# design.net
KiCad netlist of a schematic drawn in Altium Designer
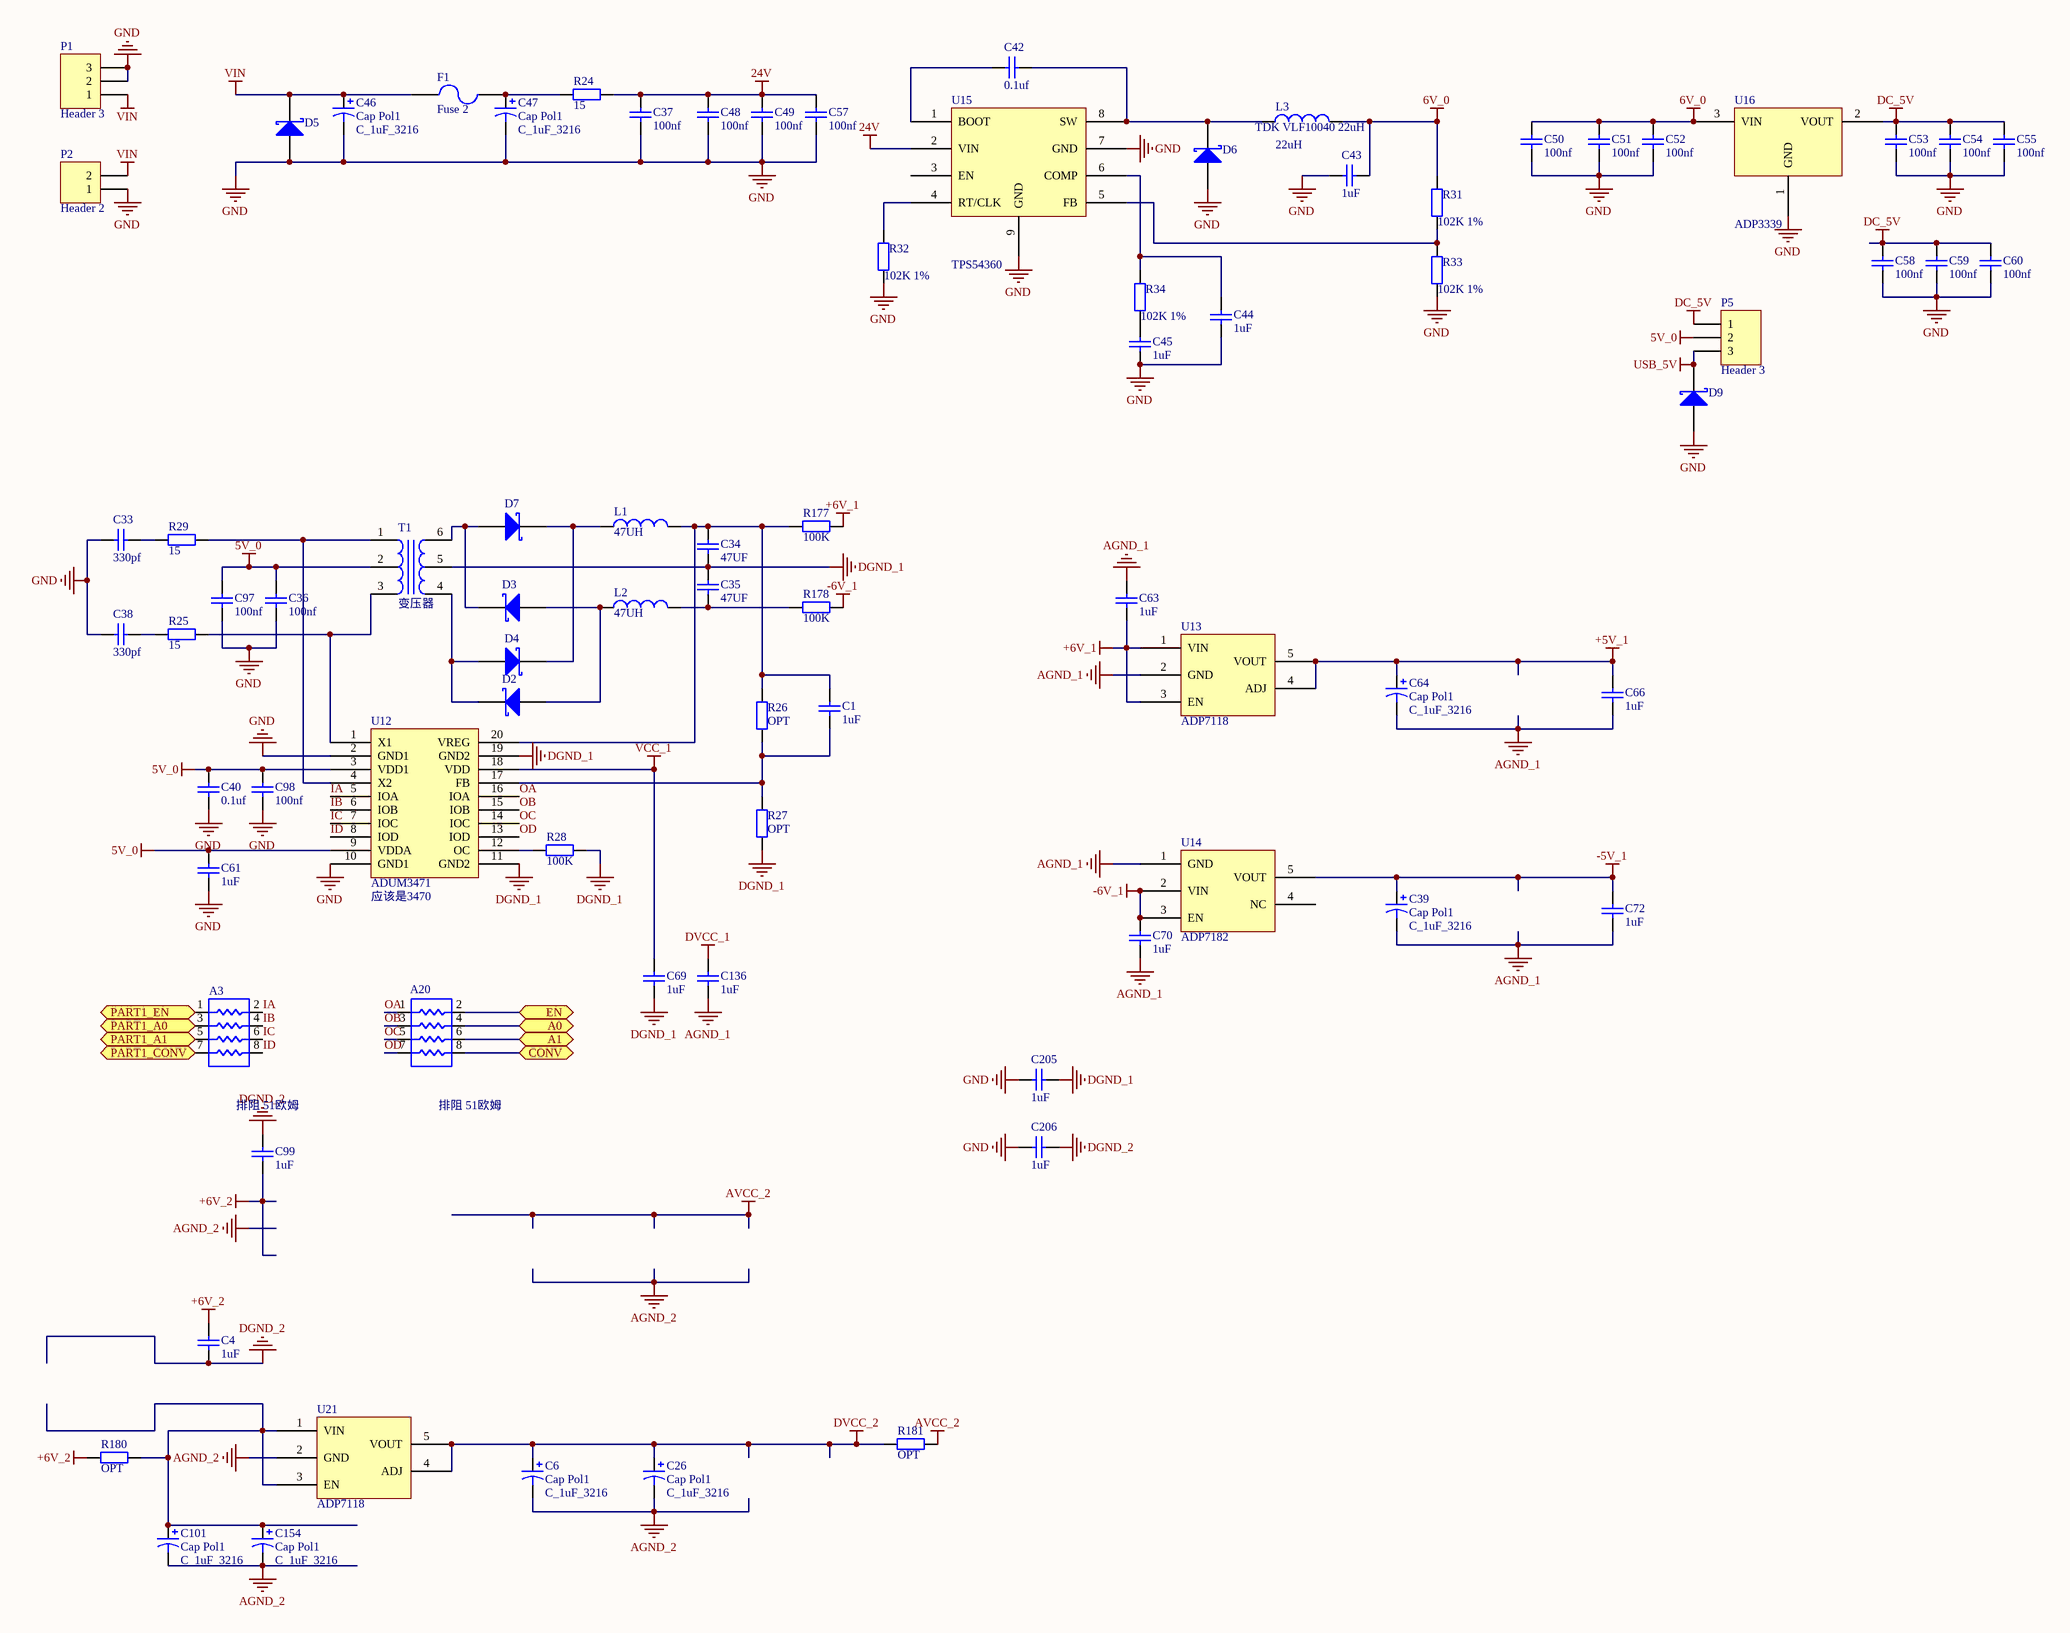
[diagram p0: 电源.SchDoc]

(export (version "E")
  (design (tool "Eeschema 10.0.6"))
  (components
    (comp (ref "A3")
      (value "排阻 51欧姆")
      (footprint "RCA03-4D")
      (libsource (lib "AD7606V23A") (part "RESPACK5"))
    )
    (comp (ref "A20")
      (value "排阻 51欧姆")
      (footprint "RCA03-4D")
      (libsource (lib "AD7606V23A") (part "RESPACK5"))
    )
    (comp (ref "C1")
      (value "1uF")
      (footprint "0805C")
      (description "Capacitor")
      (fields (field (name "PUBLISHER") "Altium Limited"))
      (libsource (lib "Miscellaneous Devices") (part "Cap"))
    )
    (comp (ref "C4")
      (value "1uF")
      (footprint "0805C")
      (description "Capacitor")
      (fields (field (name "PUBLISHER") "Altium Limited"))
      (libsource (lib "Miscellaneous Devices") (part "Cap"))
    )
    (comp (ref "C6")
      (value "Cap Pol1")
      (footprint "3216")
      (description "Polarized Capacitor (Radial)")
      (fields (field (name "ALTIUM_VALUE") "C_1uF_3216") (field (name "PUBLISHER") "Altium Limited"))
      (libsource (lib "AD7606V23A") (part "Cap Pol1"))
    )
    (comp (ref "C26")
      (value "Cap Pol1")
      (footprint "3216")
      (description "Polarized Capacitor (Radial)")
      (fields (field (name "ALTIUM_VALUE") "C_1uF_3216") (field (name "PUBLISHER") "Altium Limited"))
      (libsource (lib "AD7606V23A") (part "Cap Pol1"))
    )
    (comp (ref "C33")
      (value "330pf")
      (footprint "0805C")
      (description "Capacitor")
      (fields (field (name "Comment") "Cap") (field (name "PUBLISHER") "Altium Limited"))
      (libsource (lib "Miscellaneous Devices") (part "Cap"))
    )
    (comp (ref "C34")
      (value "47UF")
      (footprint "1812-C")
      (description "Capacitor")
      (fields (field (name "Comment") "Cap") (field (name "PUBLISHER") "Altium Limited"))
      (libsource (lib "Miscellaneous Devices") (part "Cap"))
    )
    (comp (ref "C35")
      (value "47UF")
      (footprint "1812-C")
      (description "Capacitor")
      (fields (field (name "Comment") "Cap") (field (name "PUBLISHER") "Altium Limited"))
      (libsource (lib "Miscellaneous Devices") (part "Cap"))
    )
    (comp (ref "C36")
      (value "100nf")
      (footprint "0805C")
      (description "Capacitor")
      (fields (field (name "Comment") "Cap") (field (name "PUBLISHER") "Altium Limited"))
      (libsource (lib "Miscellaneous Devices") (part "Cap"))
    )
    (comp (ref "C37")
      (value "100nf")
      (footprint "1812-C")
      (description "Capacitor")
      (fields (field (name "Comment") "Cap") (field (name "PUBLISHER") "Altium Limited"))
      (libsource (lib "Miscellaneous Devices") (part "Cap"))
    )
    (comp (ref "C38")
      (value "330pf")
      (footprint "0805C")
      (description "Capacitor")
      (fields (field (name "Comment") "Cap") (field (name "PUBLISHER") "Altium Limited"))
      (libsource (lib "Miscellaneous Devices") (part "Cap"))
    )
    (comp (ref "C39")
      (value "Cap Pol1")
      (footprint "3216")
      (description "Polarized Capacitor (Radial)")
      (fields (field (name "ALTIUM_VALUE") "C_1uF_3216") (field (name "PUBLISHER") "Altium Limited"))
      (libsource (lib "AD7606V23A") (part "Cap Pol1"))
    )
    (comp (ref "C40")
      (value "0.1uf")
      (footprint "0805C")
      (description "Capacitor")
      (fields (field (name "Comment") "Cap") (field (name "PUBLISHER") "Altium Limited"))
      (libsource (lib "Miscellaneous Devices") (part "Cap"))
    )
    (comp (ref "C42")
      (value "0.1uf")
      (footprint "独石电容")
      (description "Capacitor")
      (fields (field (name "Comment") "Cap") (field (name "PUBLISHER") "Altium Limited"))
      (libsource (lib "Miscellaneous Devices") (part "Cap"))
    )
    (comp (ref "C43")
      (value "1uF")
      (footprint "SMD-EC-F8")
      (description "Capacitor")
      (fields (field (name "PUBLISHER") "Altium Limited"))
      (libsource (lib "Miscellaneous Devices") (part "Cap"))
    )
    (comp (ref "C44")
      (value "1uF")
      (footprint "0805C")
      (description "Capacitor")
      (fields (field (name "PUBLISHER") "Altium Limited"))
      (libsource (lib "Miscellaneous Devices") (part "Cap"))
    )
    (comp (ref "C45")
      (value "1uF")
      (footprint "0805C")
      (description "Capacitor")
      (fields (field (name "PUBLISHER") "Altium Limited"))
      (libsource (lib "Miscellaneous Devices") (part "Cap"))
    )
    (comp (ref "C46")
      (value "Cap Pol1")
      (footprint "SMD-EC-F12.5")
      (description "Polarized Capacitor (Radial)")
      (fields (field (name "ALTIUM_VALUE") "C_1uF_3216") (field (name "PUBLISHER") "Altium Limited"))
      (libsource (lib "AD7606V23A") (part "Cap Pol1"))
    )
    (comp (ref "C47")
      (value "Cap Pol1")
      (footprint "0805C")
      (description "Polarized Capacitor (Radial)")
      (fields (field (name "ALTIUM_VALUE") "C_1uF_3216") (field (name "PUBLISHER") "Altium Limited"))
      (libsource (lib "AD7606V23A") (part "Cap Pol1"))
    )
    (comp (ref "C48")
      (value "100nf")
      (footprint "0805C")
      (description "Capacitor")
      (fields (field (name "Comment") "Cap") (field (name "PUBLISHER") "Altium Limited"))
      (libsource (lib "Miscellaneous Devices") (part "Cap"))
    )
    (comp (ref "C49")
      (value "100nf")
      (footprint "0805C")
      (description "Capacitor")
      (fields (field (name "Comment") "Cap") (field (name "PUBLISHER") "Altium Limited"))
      (libsource (lib "Miscellaneous Devices") (part "Cap"))
    )
    (comp (ref "C50")
      (value "100nf")
      (footprint "1812-C")
      (description "Capacitor")
      (fields (field (name "Comment") "Cap") (field (name "PUBLISHER") "Altium Limited"))
      (libsource (lib "Miscellaneous Devices") (part "Cap"))
    )
    (comp (ref "C51")
      (value "100nf")
      (footprint "0805C")
      (description "Capacitor")
      (fields (field (name "Comment") "Cap") (field (name "PUBLISHER") "Altium Limited"))
      (libsource (lib "Miscellaneous Devices") (part "Cap"))
    )
    (comp (ref "C52")
      (value "100nf")
      (footprint "0805C")
      (description "Capacitor")
      (fields (field (name "Comment") "Cap") (field (name "PUBLISHER") "Altium Limited"))
      (libsource (lib "Miscellaneous Devices") (part "Cap"))
    )
    (comp (ref "C53")
      (value "100nf")
      (footprint "1812-C")
      (description "Capacitor")
      (fields (field (name "Comment") "Cap") (field (name "PUBLISHER") "Altium Limited"))
      (libsource (lib "Miscellaneous Devices") (part "Cap"))
    )
    (comp (ref "C54")
      (value "100nf")
      (footprint "0805C")
      (description "Capacitor")
      (fields (field (name "Comment") "Cap") (field (name "PUBLISHER") "Altium Limited"))
      (libsource (lib "Miscellaneous Devices") (part "Cap"))
    )
    (comp (ref "C55")
      (value "100nf")
      (footprint "0805C")
      (description "Capacitor")
      (fields (field (name "Comment") "Cap") (field (name "PUBLISHER") "Altium Limited"))
      (libsource (lib "Miscellaneous Devices") (part "Cap"))
    )
    (comp (ref "C57")
      (value "100nf")
      (footprint "1812-C")
      (description "Capacitor")
      (fields (field (name "Comment") "Cap") (field (name "PUBLISHER") "Altium Limited"))
      (libsource (lib "Miscellaneous Devices") (part "Cap"))
    )
    (comp (ref "C58")
      (value "100nf")
      (footprint "0805C")
      (description "Capacitor")
      (fields (field (name "Comment") "Cap") (field (name "PUBLISHER") "Altium Limited"))
      (libsource (lib "Miscellaneous Devices") (part "Cap"))
    )
    (comp (ref "C59")
      (value "100nf")
      (footprint "0805C")
      (description "Capacitor")
      (fields (field (name "Comment") "Cap") (field (name "PUBLISHER") "Altium Limited"))
      (libsource (lib "Miscellaneous Devices") (part "Cap"))
    )
    (comp (ref "C60")
      (value "100nf")
      (footprint "0805C")
      (description "Capacitor")
      (fields (field (name "Comment") "Cap") (field (name "PUBLISHER") "Altium Limited"))
      (libsource (lib "Miscellaneous Devices") (part "Cap"))
    )
    (comp (ref "C61")
      (value "1uF")
      (footprint "0805C")
      (description "Capacitor")
      (fields (field (name "PUBLISHER") "Altium Limited"))
      (libsource (lib "Miscellaneous Devices") (part "Cap"))
    )
    (comp (ref "C63")
      (value "1uF")
      (footprint "0805C")
      (description "Capacitor")
      (fields (field (name "PUBLISHER") "Altium Limited"))
      (libsource (lib "Miscellaneous Devices") (part "Cap"))
    )
    (comp (ref "C64")
      (value "Cap Pol1")
      (footprint "3216")
      (description "Polarized Capacitor (Radial)")
      (fields (field (name "ALTIUM_VALUE") "C_1uF_3216") (field (name "PUBLISHER") "Altium Limited"))
      (libsource (lib "AD7606V23A") (part "Cap Pol1"))
    )
    (comp (ref "C66")
      (value "1uF")
      (footprint "0805C")
      (description "Capacitor")
      (fields (field (name "PUBLISHER") "Altium Limited"))
      (libsource (lib "Miscellaneous Devices") (part "Cap"))
    )
    (comp (ref "C69")
      (value "1uF")
      (footprint "0805C")
      (description "Capacitor")
      (fields (field (name "PUBLISHER") "Altium Limited"))
      (libsource (lib "Miscellaneous Devices") (part "Cap"))
    )
    (comp (ref "C70")
      (value "1uF")
      (footprint "0805C")
      (description "Capacitor")
      (fields (field (name "PUBLISHER") "Altium Limited"))
      (libsource (lib "Miscellaneous Devices") (part "Cap"))
    )
    (comp (ref "C72")
      (value "1uF")
      (footprint "0805C")
      (description "Capacitor")
      (fields (field (name "PUBLISHER") "Altium Limited"))
      (libsource (lib "Miscellaneous Devices") (part "Cap"))
    )
    (comp (ref "C97")
      (value "100nf")
      (footprint "0805C")
      (description "Capacitor")
      (fields (field (name "Comment") "Cap") (field (name "PUBLISHER") "Altium Limited"))
      (libsource (lib "Miscellaneous Devices") (part "Cap"))
    )
    (comp (ref "C98")
      (value "100nf")
      (footprint "0805C")
      (description "Capacitor")
      (fields (field (name "Comment") "Cap") (field (name "PUBLISHER") "Altium Limited"))
      (libsource (lib "Miscellaneous Devices") (part "Cap"))
    )
    (comp (ref "C99")
      (value "1uF")
      (footprint "0805C")
      (description "Capacitor")
      (fields (field (name "PUBLISHER") "Altium Limited"))
      (libsource (lib "Miscellaneous Devices") (part "Cap"))
    )
    (comp (ref "C101")
      (value "Cap Pol1")
      (footprint "3216")
      (description "Polarized Capacitor (Radial)")
      (fields (field (name "ALTIUM_VALUE") "C_1uF_3216") (field (name "PUBLISHER") "Altium Limited"))
      (libsource (lib "AD7606V23A") (part "Cap Pol1"))
    )
    (comp (ref "C136")
      (value "1uF")
      (footprint "0805C")
      (description "Capacitor")
      (fields (field (name "PUBLISHER") "Altium Limited"))
      (libsource (lib "Miscellaneous Devices") (part "Cap"))
    )
    (comp (ref "C154")
      (value "Cap Pol1")
      (footprint "3216")
      (description "Polarized Capacitor (Radial)")
      (fields (field (name "ALTIUM_VALUE") "C_1uF_3216") (field (name "PUBLISHER") "Altium Limited"))
      (libsource (lib "AD7606V23A") (part "Cap Pol1"))
    )
    (comp (ref "C205")
      (value "1uF")
      (footprint "7.5mm-C")
      (description "Capacitor")
      (fields (field (name "PUBLISHER") "Altium Limited"))
      (libsource (lib "Miscellaneous Devices") (part "Cap"))
    )
    (comp (ref "C206")
      (value "1uF")
      (footprint "7.5mm-C")
      (description "Capacitor")
      (fields (field (name "PUBLISHER") "Altium Limited"))
      (libsource (lib "Miscellaneous Devices") (part "Cap"))
    )
    (comp (ref "D2")
      (value "~")
      (footprint "FB1206")
      (description "Schottky Rectifier")
      (fields (field (name "PUBLISHER") "Altium Limited"))
      (libsource (lib "Miscellaneous Devices") (part "Diode 11DQ03"))
    )
    (comp (ref "D3")
      (value "~")
      (footprint "FB1206")
      (description "Schottky Rectifier")
      (fields (field (name "PUBLISHER") "Altium Limited"))
      (libsource (lib "Miscellaneous Devices") (part "Diode 11DQ03"))
    )
    (comp (ref "D4")
      (value "~")
      (footprint "FB1206")
      (description "Schottky Rectifier")
      (fields (field (name "PUBLISHER") "Altium Limited"))
      (libsource (lib "Miscellaneous Devices") (part "Diode 11DQ03"))
    )
    (comp (ref "D5")
      (value "~")
      (footprint "SMB1")
      (description "Schottky Rectifier")
      (fields (field (name "PUBLISHER") "Altium Limited"))
      (libsource (lib "Miscellaneous Devices") (part "Diode 11DQ03"))
    )
    (comp (ref "D6")
      (value "~")
      (footprint "SMA")
      (description "Schottky Rectifier")
      (fields (field (name "PUBLISHER") "Altium Limited"))
      (libsource (lib "Miscellaneous Devices") (part "Diode 11DQ03"))
    )
    (comp (ref "D7")
      (value "~")
      (footprint "FB1206")
      (description "Schottky Rectifier")
      (fields (field (name "PUBLISHER") "Altium Limited"))
      (libsource (lib "Miscellaneous Devices") (part "Diode 11DQ03"))
    )
    (comp (ref "D9")
      (value "~")
      (footprint "SMA")
      (description "Schottky Rectifier")
      (fields (field (name "PUBLISHER") "Altium Limited"))
      (libsource (lib "Miscellaneous Devices") (part "Diode 11DQ03"))
    )
    (comp (ref "F1")
      (value "Fuse 2")
      (footprint "1812-PPTC")
      (description "Fuse")
      (fields (field (name "PUBLISHER") "Altium Limited"))
      (libsource (lib "Miscellaneous Devices") (part "Fuse 2"))
    )
    (comp (ref "L1")
      (value "47UH")
      (footprint "1812-R")
      (description "Inductor")
      (fields (field (name "PUBLISHER") "Altium Limited"))
      (libsource (lib "Miscellaneous Devices") (part "Inductor"))
    )
    (comp (ref "L2")
      (value "47UH")
      (footprint "1812-R")
      (description "Inductor")
      (fields (field (name "PUBLISHER") "Altium Limited"))
      (libsource (lib "Miscellaneous Devices") (part "Inductor"))
    )
    (comp (ref "L3")
      (value "TDK VLF10040 22uH")
      (footprint "RH74")
      (description "Inductor")
      (fields (field (name "ALTIUM_VALUE") "22uH") (field (name "PUBLISHER") "Altium Limited"))
      (libsource (lib "Miscellaneous Devices") (part "Inductor"))
    )
    (comp (ref "P1")
      (value "Header 3")
      (footprint "DC-005A")
      (description "Header, 3-Pin")
      (fields (field (name "PUBLISHER") "Altium Limited"))
      (libsource (lib "Miscellaneous Connectors") (part "Header 3"))
    )
    (comp (ref "P2")
      (value "Header 2")
      (footprint "2EDGK-2P")
      (description "Header, 2-Pin")
      (fields (field (name "PUBLISHER") "Altium Limited"))
      (libsource (lib "Miscellaneous Connectors") (part "Header 2"))
    )
    (comp (ref "P5")
      (value "Header 3")
      (footprint "SIP03")
      (description "Header, 3-Pin")
      (fields (field (name "PUBLISHER") "Altium Limited"))
      (libsource (lib "") (part "Header 3_1"))
    )
    (comp (ref "R24")
      (value "15")
      (footprint "FB1206")
      (description "Resistor")
      (fields (field (name "Comment") "Res2") (field (name "PUBLISHER") "Altium Limited"))
      (libsource (lib "") (part "Res2_2"))
    )
    (comp (ref "R25")
      (value "15")
      (footprint "0805R")
      (description "Resistor")
      (fields (field (name "Comment") "Res2") (field (name "PUBLISHER") "Altium Limited"))
      (libsource (lib "") (part "Res2_2"))
    )
    (comp (ref "R26")
      (value "OPT")
      (footprint "0805R")
      (description "Resistor")
      (fields (field (name "Comment") "Res2") (field (name "PUBLISHER") "Altium Limited"))
      (libsource (lib "") (part "Res2_1"))
    )
    (comp (ref "R27")
      (value "OPT")
      (footprint "0805R")
      (description "Resistor")
      (fields (field (name "Comment") "Res2") (field (name "PUBLISHER") "Altium Limited"))
      (libsource (lib "") (part "Res2_1"))
    )
    (comp (ref "R28")
      (value "100K")
      (footprint "0805R")
      (description "Resistor")
      (fields (field (name "Comment") "Res2") (field (name "PUBLISHER") "Altium Limited"))
      (libsource (lib "") (part "Res2_2"))
    )
    (comp (ref "R29")
      (value "15")
      (footprint "0805R")
      (description "Resistor")
      (fields (field (name "Comment") "Res2") (field (name "PUBLISHER") "Altium Limited"))
      (libsource (lib "") (part "Res2_2"))
    )
    (comp (ref "R31")
      (value "102K 1%")
      (footprint "0805R")
      (description "Resistor")
      (fields (field (name "PUBLISHER") "Altium Limited"))
      (libsource (lib "Miscellaneous Devices") (part "Res2"))
    )
    (comp (ref "R32")
      (value "102K 1%")
      (footprint "0805R")
      (description "Resistor")
      (fields (field (name "PUBLISHER") "Altium Limited"))
      (libsource (lib "Miscellaneous Devices") (part "Res2"))
    )
    (comp (ref "R33")
      (value "102K 1%")
      (footprint "0805R")
      (description "Resistor")
      (fields (field (name "PUBLISHER") "Altium Limited"))
      (libsource (lib "Miscellaneous Devices") (part "Res2"))
    )
    (comp (ref "R34")
      (value "102K 1%")
      (footprint "0805R")
      (description "Resistor")
      (fields (field (name "PUBLISHER") "Altium Limited"))
      (libsource (lib "Miscellaneous Devices") (part "Res2"))
    )
    (comp (ref "R177")
      (value "100K")
      (footprint "0805R")
      (description "Resistor")
      (fields (field (name "Comment") "Res2") (field (name "PUBLISHER") "Altium Limited"))
      (libsource (lib "") (part "Res2_2"))
    )
    (comp (ref "R178")
      (value "100K")
      (footprint "0805R")
      (description "Resistor")
      (fields (field (name "Comment") "Res2") (field (name "PUBLISHER") "Altium Limited"))
      (libsource (lib "") (part "Res2_2"))
    )
    (comp (ref "R180")
      (value "OPT")
      (footprint "0805R")
      (description "Resistor")
      (fields (field (name "Comment") "Res2") (field (name "PUBLISHER") "Altium Limited"))
      (libsource (lib "") (part "Res2_2"))
    )
    (comp (ref "R181")
      (value "OPT")
      (footprint "0805R")
      (description "Resistor")
      (fields (field (name "Comment") "Res2") (field (name "PUBLISHER") "Altium Limited"))
      (libsource (lib "") (part "Res2_2"))
    )
    (comp (ref "T1") (value "变压器") (footprint "变压器") (libsource (lib "ic_lib") (part "变压器")))
    (comp (ref "U12") (value "ADUM3471") (footprint "SSOP20") (libsource (lib "ic_lib") (part "ADUM3471")))
    (comp (ref "U13") (value "ADP7118") (footprint "SOT-23-5") (libsource (lib "ic_lib") (part "ADP7118")))
    (comp (ref "U14") (value "ADP7182") (footprint "SOT-23-5") (libsource (lib "ic_lib") (part "ADP7182")))
    (comp (ref "U15") (value "TPS54360") (footprint "TPS54360") (libsource (lib "ic_lib") (part "TPS54360")))
    (comp (ref "U16") (value "ADP3339") (footprint "_SOT-223") (libsource (lib "ic_lib") (part "ADP3339")))
    (comp (ref "U21") (value "ADP7118") (footprint "SOT-23-5") (libsource (lib "ic_lib") (part "ADP7118")))
  )
  (nets
    (net (code "1") (name "+5V_1") (class "Default")
      (node (ref "C64") (pin "1") (pinfunction "1_1") (pintype "passive"))
      (node (ref "C66") (pin "1") (pinfunction "1_1") (pintype "passive"))
      (node (ref "U13") (pin "4") (pinfunction "ADJ_4") (pintype "passive"))
      (node (ref "U13") (pin "5") (pinfunction "VOUT_5") (pintype "passive"))
    )
    (net (code "2") (name "+6V_1") (class "Default")
      (node (ref "C63") (pin "2") (pinfunction "2_2") (pintype "passive"))
      (node (ref "R177") (pin "2") (pinfunction "2_2") (pintype "passive"))
      (node (ref "U13") (pin "1") (pinfunction "VIN_1") (pintype "passive"))
      (node (ref "U13") (pin "3") (pinfunction "EN_3") (pintype "passive"))
    )
    (net (code "3") (name "+6V_2") (class "Default")
      (node (ref "C4") (pin "1") (pinfunction "1_1") (pintype "passive"))
      (node (ref "C99") (pin "2") (pinfunction "2_2") (pintype "passive"))
      (node (ref "R180") (pin "1") (pinfunction "1_1") (pintype "passive"))
    )
    (net (code "4") (name "-5V_1") (class "Default")
      (node (ref "C39") (pin "1") (pinfunction "1_1") (pintype "passive"))
      (node (ref "C72") (pin "1") (pinfunction "1_1") (pintype "passive"))
      (node (ref "U14") (pin "5") (pinfunction "VOUT_5") (pintype "passive"))
    )
    (net (code "5") (name "-6V_1") (class "Default")
      (node (ref "C70") (pin "1") (pinfunction "1_1") (pintype "passive"))
      (node (ref "R178") (pin "2") (pinfunction "2_2") (pintype "passive"))
      (node (ref "U14") (pin "2") (pinfunction "VIN_2") (pintype "passive"))
      (node (ref "U14") (pin "3") (pinfunction "EN_3") (pintype "passive"))
    )
    (net (code "6") (name "/A0") (class "Default")
      (node (ref "A20") (pin "4") (pinfunction "4_4") (pintype "passive"))
    )
    (net (code "7") (name "/A1") (class "Default")
      (node (ref "A20") (pin "6") (pinfunction "8_6") (pintype "passive"))
    )
    (net (code "8") (name "/CONV") (class "Default")
      (node (ref "A20") (pin "8") (pinfunction "8_8") (pintype "passive"))
    )
    (net (code "9") (name "/EN") (class "Default")
      (node (ref "A20") (pin "2") (pinfunction "2_2") (pintype "passive"))
    )
    (net (code "10") (name "/IA") (class "Default")
      (node (ref "A3") (pin "2") (pinfunction "2_2") (pintype "passive"))
      (node (ref "U12") (pin "5") (pinfunction "IOA_5") (pintype "passive"))
    )
    (net (code "11") (name "/IB") (class "Default")
      (node (ref "A3") (pin "4") (pinfunction "4_4") (pintype "passive"))
      (node (ref "U12") (pin "6") (pinfunction "IOB_6") (pintype "passive"))
    )
    (net (code "12") (name "/IC") (class "Default")
      (node (ref "A3") (pin "6") (pinfunction "8_6") (pintype "passive"))
      (node (ref "U12") (pin "7") (pinfunction "IOC_7") (pintype "passive"))
    )
    (net (code "13") (name "/ID") (class "Default")
      (node (ref "A3") (pin "8") (pinfunction "8_8") (pintype "passive"))
      (node (ref "U12") (pin "8") (pinfunction "IOD_8") (pintype "passive"))
    )
    (net (code "14") (name "/OA") (class "Default")
      (node (ref "A20") (pin "1") (pinfunction "1_1") (pintype "passive"))
      (node (ref "U12") (pin "16") (pinfunction "IOA_16") (pintype "passive"))
    )
    (net (code "15") (name "/OB") (class "Default")
      (node (ref "A20") (pin "3") (pinfunction "3_3") (pintype "passive"))
      (node (ref "U12") (pin "15") (pinfunction "IOB_15") (pintype "passive"))
    )
    (net (code "16") (name "/OC") (class "Default")
      (node (ref "A20") (pin "5") (pinfunction "5_5") (pintype "passive"))
      (node (ref "U12") (pin "14") (pinfunction "IOC_14") (pintype "passive"))
    )
    (net (code "17") (name "/OD") (class "Default")
      (node (ref "A20") (pin "7") (pinfunction "7_7") (pintype "passive"))
      (node (ref "U12") (pin "13") (pinfunction "IOD_13") (pintype "passive"))
    )
    (net (code "18") (name "/PART1_A0") (class "Default")
      (node (ref "A3") (pin "3") (pinfunction "3_3") (pintype "passive"))
    )
    (net (code "19") (name "/PART1_A1") (class "Default")
      (node (ref "A3") (pin "5") (pinfunction "5_5") (pintype "passive"))
    )
    (net (code "20") (name "/PART1_CONV") (class "Default")
      (node (ref "A3") (pin "7") (pinfunction "7_7") (pintype "passive"))
    )
    (net (code "21") (name "/PART1_EN") (class "Default")
      (node (ref "A3") (pin "1") (pinfunction "1_1") (pintype "passive"))
    )
    (net (code "22") (name "5V_0") (class "Default")
      (node (ref "C36") (pin "2") (pinfunction "2_2") (pintype "passive"))
      (node (ref "C40") (pin "1") (pinfunction "1_1") (pintype "passive"))
      (node (ref "C61") (pin "1") (pinfunction "1_1") (pintype "passive"))
      (node (ref "C97") (pin "2") (pinfunction "2_2") (pintype "passive"))
      (node (ref "C98") (pin "2") (pinfunction "2_2") (pintype "passive"))
      (node (ref "P5") (pin "2") (pinfunction "2_2") (pintype "passive"))
      (node (ref "T1") (pin "2") (pinfunction "2_2") (pintype "passive"))
      (node (ref "U12") (pin "3") (pinfunction "VDD1_3") (pintype "passive"))
      (node (ref "U12") (pin "9") (pinfunction "VDDA_9") (pintype "passive"))
    )
    (net (code "23") (name "6V_0") (class "Default")
      (node (ref "C43") (pin "1") (pinfunction "1_1") (pintype "passive"))
      (node (ref "C50") (pin "2") (pinfunction "2_2") (pintype "passive"))
      (node (ref "C51") (pin "2") (pinfunction "2_2") (pintype "passive"))
      (node (ref "C52") (pin "2") (pinfunction "2_2") (pintype "passive"))
      (node (ref "L3") (pin "2") (pinfunction "2_2") (pintype "passive"))
      (node (ref "R31") (pin "2") (pinfunction "2_2") (pintype "passive"))
      (node (ref "U16") (pin "3") (pinfunction "VIN_3") (pintype "passive"))
    )
    (net (code "24") (name "24V") (class "Default")
      (node (ref "C37") (pin "2") (pinfunction "2_2") (pintype "passive"))
      (node (ref "C48") (pin "2") (pinfunction "2_2") (pintype "passive"))
      (node (ref "C49") (pin "2") (pinfunction "2_2") (pintype "passive"))
      (node (ref "C57") (pin "2") (pinfunction "2_2") (pintype "passive"))
      (node (ref "R24") (pin "2") (pinfunction "2_2") (pintype "passive"))
      (node (ref "U15") (pin "2") (pinfunction "VIN_2") (pintype "passive"))
    )
    (net (code "25") (name "AGND_1") (class "Default")
      (node (ref "C136") (pin "2") (pinfunction "2_2") (pintype "passive"))
      (node (ref "C39") (pin "2") (pinfunction "2_2") (pintype "passive"))
      (node (ref "C63") (pin "1") (pinfunction "1_1") (pintype "passive"))
      (node (ref "C64") (pin "2") (pinfunction "2_2") (pintype "passive"))
      (node (ref "C66") (pin "2") (pinfunction "2_2") (pintype "passive"))
      (node (ref "C70") (pin "2") (pinfunction "2_2") (pintype "passive"))
      (node (ref "C72") (pin "2") (pinfunction "2_2") (pintype "passive"))
      (node (ref "U13") (pin "2") (pinfunction "GND_2") (pintype "passive"))
      (node (ref "U14") (pin "1") (pinfunction "GND_1") (pintype "passive"))
    )
    (net (code "26") (name "AGND_2") (class "Default")
      (node (ref "C101") (pin "2") (pinfunction "2_2") (pintype "passive"))
      (node (ref "C154") (pin "2") (pinfunction "2_2") (pintype "passive"))
      (node (ref "C26") (pin "2") (pinfunction "2_2") (pintype "passive"))
      (node (ref "C6") (pin "2") (pinfunction "2_2") (pintype "passive"))
      (node (ref "U21") (pin "2") (pinfunction "GND_2") (pintype "passive"))
    )
    (net (code "27") (name "AVCC_2") (class "Default")
      (node (ref "R181") (pin "2") (pinfunction "2_2") (pintype "passive"))
    )
    (net (code "28") (name "DC_5V") (class "Default")
      (node (ref "C53") (pin "2") (pinfunction "2_2") (pintype "passive"))
      (node (ref "C54") (pin "2") (pinfunction "2_2") (pintype "passive"))
      (node (ref "C55") (pin "2") (pinfunction "2_2") (pintype "passive"))
      (node (ref "C58") (pin "2") (pinfunction "2_2") (pintype "passive"))
      (node (ref "C59") (pin "2") (pinfunction "2_2") (pintype "passive"))
      (node (ref "C60") (pin "2") (pinfunction "2_2") (pintype "passive"))
      (node (ref "P5") (pin "1") (pinfunction "1_1") (pintype "passive"))
      (node (ref "U16") (pin "2") (pinfunction "VOUT_2") (pintype "passive"))
    )
    (net (code "29") (name "DGND_1") (class "Default")
      (node (ref "C205") (pin "2") (pinfunction "2_2") (pintype "passive"))
      (node (ref "C34") (pin "1") (pinfunction "1_1") (pintype "passive"))
      (node (ref "C35") (pin "2") (pinfunction "2_2") (pintype "passive"))
      (node (ref "C69") (pin "2") (pinfunction "2_2") (pintype "passive"))
      (node (ref "R27") (pin "2") (pinfunction "2_2") (pintype "passive"))
      (node (ref "R28") (pin "2") (pinfunction "2_2") (pintype "passive"))
      (node (ref "T1") (pin "5") (pinfunction "5_5") (pintype "passive"))
      (node (ref "U12") (pin "11") (pinfunction "GND2_11") (pintype "passive"))
      (node (ref "U12") (pin "19") (pinfunction "GND2_19") (pintype "passive"))
    )
    (net (code "30") (name "DGND_2") (class "Default")
      (node (ref "C206") (pin "2") (pinfunction "2_2") (pintype "passive"))
      (node (ref "C4") (pin "2") (pinfunction "2_2") (pintype "passive"))
      (node (ref "C99") (pin "1") (pinfunction "1_1") (pintype "passive"))
    )
    (net (code "31") (name "DVCC_1") (class "Default")
      (node (ref "C136") (pin "1") (pinfunction "1_1") (pintype "passive"))
    )
    (net (code "32") (name "DVCC_2") (class "Default")
      (node (ref "C26") (pin "1") (pinfunction "1_1") (pintype "passive"))
      (node (ref "C6") (pin "1") (pinfunction "1_1") (pintype "passive"))
      (node (ref "R181") (pin "1") (pinfunction "1_1") (pintype "passive"))
      (node (ref "U21") (pin "4") (pinfunction "ADJ_4") (pintype "passive"))
      (node (ref "U21") (pin "5") (pinfunction "VOUT_5") (pintype "passive"))
    )
    (net (code "33") (name "GND") (class "Default")
      (node (ref "C205") (pin "1") (pinfunction "1_1") (pintype "passive"))
      (node (ref "C206") (pin "1") (pinfunction "1_1") (pintype "passive"))
      (node (ref "C33") (pin "1") (pinfunction "1_1") (pintype "passive"))
      (node (ref "C36") (pin "1") (pinfunction "1_1") (pintype "passive"))
      (node (ref "C37") (pin "1") (pinfunction "1_1") (pintype "passive"))
      (node (ref "C38") (pin "1") (pinfunction "1_1") (pintype "passive"))
      (node (ref "C40") (pin "2") (pinfunction "2_2") (pintype "passive"))
      (node (ref "C43") (pin "2") (pinfunction "2_2") (pintype "passive"))
      (node (ref "C44") (pin "2") (pinfunction "2_2") (pintype "passive"))
      (node (ref "C45") (pin "2") (pinfunction "2_2") (pintype "passive"))
      (node (ref "C46") (pin "2") (pinfunction "2_2") (pintype "passive"))
      (node (ref "C47") (pin "2") (pinfunction "2_2") (pintype "passive"))
      (node (ref "C48") (pin "1") (pinfunction "1_1") (pintype "passive"))
      (node (ref "C49") (pin "1") (pinfunction "1_1") (pintype "passive"))
      (node (ref "C50") (pin "1") (pinfunction "1_1") (pintype "passive"))
      (node (ref "C51") (pin "1") (pinfunction "1_1") (pintype "passive"))
      (node (ref "C52") (pin "1") (pinfunction "1_1") (pintype "passive"))
      (node (ref "C53") (pin "1") (pinfunction "1_1") (pintype "passive"))
      (node (ref "C54") (pin "1") (pinfunction "1_1") (pintype "passive"))
      (node (ref "C55") (pin "1") (pinfunction "1_1") (pintype "passive"))
      (node (ref "C57") (pin "1") (pinfunction "1_1") (pintype "passive"))
      (node (ref "C58") (pin "1") (pinfunction "1_1") (pintype "passive"))
      (node (ref "C59") (pin "1") (pinfunction "1_1") (pintype "passive"))
      (node (ref "C60") (pin "1") (pinfunction "1_1") (pintype "passive"))
      (node (ref "C61") (pin "2") (pinfunction "2_2") (pintype "passive"))
      (node (ref "C97") (pin "1") (pinfunction "1_1") (pintype "passive"))
      (node (ref "C98") (pin "1") (pinfunction "1_1") (pintype "passive"))
      (node (ref "D5") (pin "1") (pinfunction "A_1") (pintype "passive"))
      (node (ref "D6") (pin "1") (pinfunction "A_1") (pintype "passive"))
      (node (ref "D9") (pin "1") (pinfunction "A_1") (pintype "passive"))
      (node (ref "P1") (pin "2") (pinfunction "2_2") (pintype "passive"))
      (node (ref "P1") (pin "3") (pinfunction "3_3") (pintype "passive"))
      (node (ref "P2") (pin "1") (pinfunction "1_1") (pintype "passive"))
      (node (ref "R32") (pin "1") (pinfunction "1_1") (pintype "passive"))
      (node (ref "R33") (pin "1") (pinfunction "1_1") (pintype "passive"))
      (node (ref "U12") (pin "10") (pinfunction "GND1_10") (pintype "passive"))
      (node (ref "U12") (pin "2") (pinfunction "GND1_2") (pintype "passive"))
      (node (ref "U15") (pin "7") (pinfunction "GND_7") (pintype "passive"))
      (node (ref "U15") (pin "9") (pinfunction "GND_9") (pintype "passive"))
      (node (ref "U16") (pin "1") (pinfunction "GND_1") (pintype "passive"))
    )
    (net (code "34") (name "Net-(C33-Pad2)") (class "Default")
      (node (ref "C33") (pin "2") (pinfunction "2_2") (pintype "passive"))
      (node (ref "R29") (pin "1") (pinfunction "1_1") (pintype "passive"))
    )
    (net (code "35") (name "Net-(C35-Pad1)") (class "Default")
      (node (ref "C35") (pin "1") (pinfunction "1_1") (pintype "passive"))
      (node (ref "L2") (pin "2") (pinfunction "2_2") (pintype "passive"))
      (node (ref "R178") (pin "1") (pinfunction "1_1") (pintype "passive"))
    )
    (net (code "36") (name "Net-(C38-Pad2)") (class "Default")
      (node (ref "C38") (pin "2") (pinfunction "2_2") (pintype "passive"))
      (node (ref "R25") (pin "1") (pinfunction "1_1") (pintype "passive"))
    )
    (net (code "37") (name "Net-(C45-Pad1)") (class "Default")
      (node (ref "C45") (pin "1") (pinfunction "1_1") (pintype "passive"))
      (node (ref "R34") (pin "1") (pinfunction "1_1") (pintype "passive"))
    )
    (net (code "38") (name "Net-(C47-Pad1)") (class "Default")
      (node (ref "C47") (pin "1") (pinfunction "1_1") (pintype "passive"))
      (node (ref "F1") (pin "2") (pinfunction "2_2") (pintype "passive"))
      (node (ref "R24") (pin "1") (pinfunction "1_1") (pintype "passive"))
    )
    (net (code "39") (name "Net-(D2-A)") (class "Default")
      (node (ref "D2") (pin "1") (pinfunction "A_1") (pintype "passive"))
      (node (ref "D3") (pin "1") (pinfunction "A_1") (pintype "passive"))
      (node (ref "L2") (pin "1") (pinfunction "1_1") (pintype "passive"))
    )
    (net (code "40") (name "Net-(D2-K)") (class "Default")
      (node (ref "D2") (pin "2") (pinfunction "K_2") (pintype "passive"))
      (node (ref "D4") (pin "1") (pinfunction "A_1") (pintype "passive"))
      (node (ref "T1") (pin "4") (pinfunction "4_4") (pintype "passive"))
    )
    (net (code "41") (name "Net-(D3-K)") (class "Default")
      (node (ref "D3") (pin "2") (pinfunction "K_2") (pintype "passive"))
      (node (ref "D7") (pin "1") (pinfunction "A_1") (pintype "passive"))
      (node (ref "T1") (pin "6") (pinfunction "6_6") (pintype "passive"))
    )
    (net (code "42") (name "Net-(D4-K)") (class "Default")
      (node (ref "D4") (pin "2") (pinfunction "K_2") (pintype "passive"))
      (node (ref "D7") (pin "2") (pinfunction "K_2") (pintype "passive"))
      (node (ref "L1") (pin "1") (pinfunction "1_1") (pintype "passive"))
    )
    (net (code "43") (name "Net-(D6-K)") (class "Default")
      (node (ref "C42") (pin "2") (pinfunction "2_2") (pintype "passive"))
      (node (ref "D6") (pin "2") (pinfunction "K_2") (pintype "passive"))
      (node (ref "L3") (pin "1") (pinfunction "1_1") (pintype "passive"))
      (node (ref "U15") (pin "8") (pinfunction "SW_8") (pintype "passive"))
    )
    (net (code "44") (name "Net-(U12-FB)") (class "Default")
      (node (ref "C1") (pin "2") (pinfunction "2_2") (pintype "passive"))
      (node (ref "R26") (pin "2") (pinfunction "2_2") (pintype "passive"))
      (node (ref "R27") (pin "1") (pinfunction "1_1") (pintype "passive"))
      (node (ref "U12") (pin "17") (pinfunction "FB_17") (pintype "passive"))
    )
    (net (code "45") (name "Net-(U12-OC)") (class "Default")
      (node (ref "R28") (pin "1") (pinfunction "1_1") (pintype "passive"))
      (node (ref "U12") (pin "12") (pinfunction "OC_12") (pintype "passive"))
    )
    (net (code "46") (name "Net-(U12-VREG)") (class "Default")
      (node (ref "C1") (pin "1") (pinfunction "1_1") (pintype "passive"))
      (node (ref "C34") (pin "2") (pinfunction "2_2") (pintype "passive"))
      (node (ref "L1") (pin "2") (pinfunction "2_2") (pintype "passive"))
      (node (ref "R177") (pin "1") (pinfunction "1_1") (pintype "passive"))
      (node (ref "R26") (pin "1") (pinfunction "1_1") (pintype "passive"))
      (node (ref "U12") (pin "20") (pinfunction "VREG_20") (pintype "passive"))
    )
    (net (code "47") (name "Net-(U12-X1)") (class "Default")
      (node (ref "R25") (pin "2") (pinfunction "2_2") (pintype "passive"))
      (node (ref "T1") (pin "3") (pinfunction "3_3") (pintype "passive"))
      (node (ref "U12") (pin "1") (pinfunction "X1_1") (pintype "passive"))
    )
    (net (code "48") (name "Net-(U12-X2)") (class "Default")
      (node (ref "R29") (pin "2") (pinfunction "2_2") (pintype "passive"))
      (node (ref "T1") (pin "1") (pinfunction "1_1") (pintype "passive"))
      (node (ref "U12") (pin "4") (pinfunction "X2_4") (pintype "passive"))
    )
    (net (code "49") (name "Net-(U15-BOOT)") (class "Default")
      (node (ref "C42") (pin "1") (pinfunction "1_1") (pintype "passive"))
      (node (ref "U15") (pin "1") (pinfunction "BOOT_1") (pintype "passive"))
    )
    (net (code "50") (name "Net-(U15-COMP)") (class "Default")
      (node (ref "C44") (pin "1") (pinfunction "1_1") (pintype "passive"))
      (node (ref "R34") (pin "2") (pinfunction "2_2") (pintype "passive"))
      (node (ref "U15") (pin "6") (pinfunction "COMP_6") (pintype "passive"))
    )
    (net (code "51") (name "Net-(U15-FB)") (class "Default")
      (node (ref "R31") (pin "1") (pinfunction "1_1") (pintype "passive"))
      (node (ref "R33") (pin "2") (pinfunction "2_2") (pintype "passive"))
      (node (ref "U15") (pin "5") (pinfunction "FB_5") (pintype "passive"))
    )
    (net (code "52") (name "Net-(U15-RT{slash}CLK)") (class "Default")
      (node (ref "R32") (pin "2") (pinfunction "2_2") (pintype "passive"))
      (node (ref "U15") (pin "4") (pinfunction "RT/CLK_4") (pintype "passive"))
    )
    (net (code "53") (name "Net-(U21-EN)") (class "Default")
      (node (ref "C101") (pin "1") (pinfunction "1_1") (pintype "passive"))
      (node (ref "C154") (pin "1") (pinfunction "1_1") (pintype "passive"))
      (node (ref "R180") (pin "2") (pinfunction "2_2") (pintype "passive"))
      (node (ref "U21") (pin "1") (pinfunction "VIN_1") (pintype "passive"))
      (node (ref "U21") (pin "3") (pinfunction "EN_3") (pintype "passive"))
    )
    (net (code "54") (name "USB_5V") (class "Default")
      (node (ref "D9") (pin "2") (pinfunction "K_2") (pintype "passive"))
      (node (ref "P5") (pin "3") (pinfunction "3_3") (pintype "passive"))
    )
    (net (code "55") (name "VCC_1") (class "Default")
      (node (ref "C69") (pin "1") (pinfunction "1_1") (pintype "passive"))
      (node (ref "U12") (pin "18") (pinfunction "VDD_18") (pintype "passive"))
    )
    (net (code "56") (name "VIN") (class "Default")
      (node (ref "C46") (pin "1") (pinfunction "1_1") (pintype "passive"))
      (node (ref "D5") (pin "2") (pinfunction "K_2") (pintype "passive"))
      (node (ref "F1") (pin "1") (pinfunction "1_1") (pintype "passive"))
      (node (ref "P1") (pin "1") (pinfunction "1_1") (pintype "passive"))
      (node (ref "P2") (pin "2") (pinfunction "2_2") (pintype "passive"))
    )
    (net (code "57") (name "unconnected-(U14-NC-Pad4)") (class "Default")
      (node (ref "U14") (pin "4") (pinfunction "NC_4") (pintype "passive"))
    )
    (net (code "58") (name "unconnected-(U15-EN-Pad3)") (class "Default")
      (node (ref "U15") (pin "3") (pinfunction "EN_3") (pintype "passive"))
    )
  )
)
